# STM32F429.net
KiCad netlist of a schematic drawn in Altium Designer
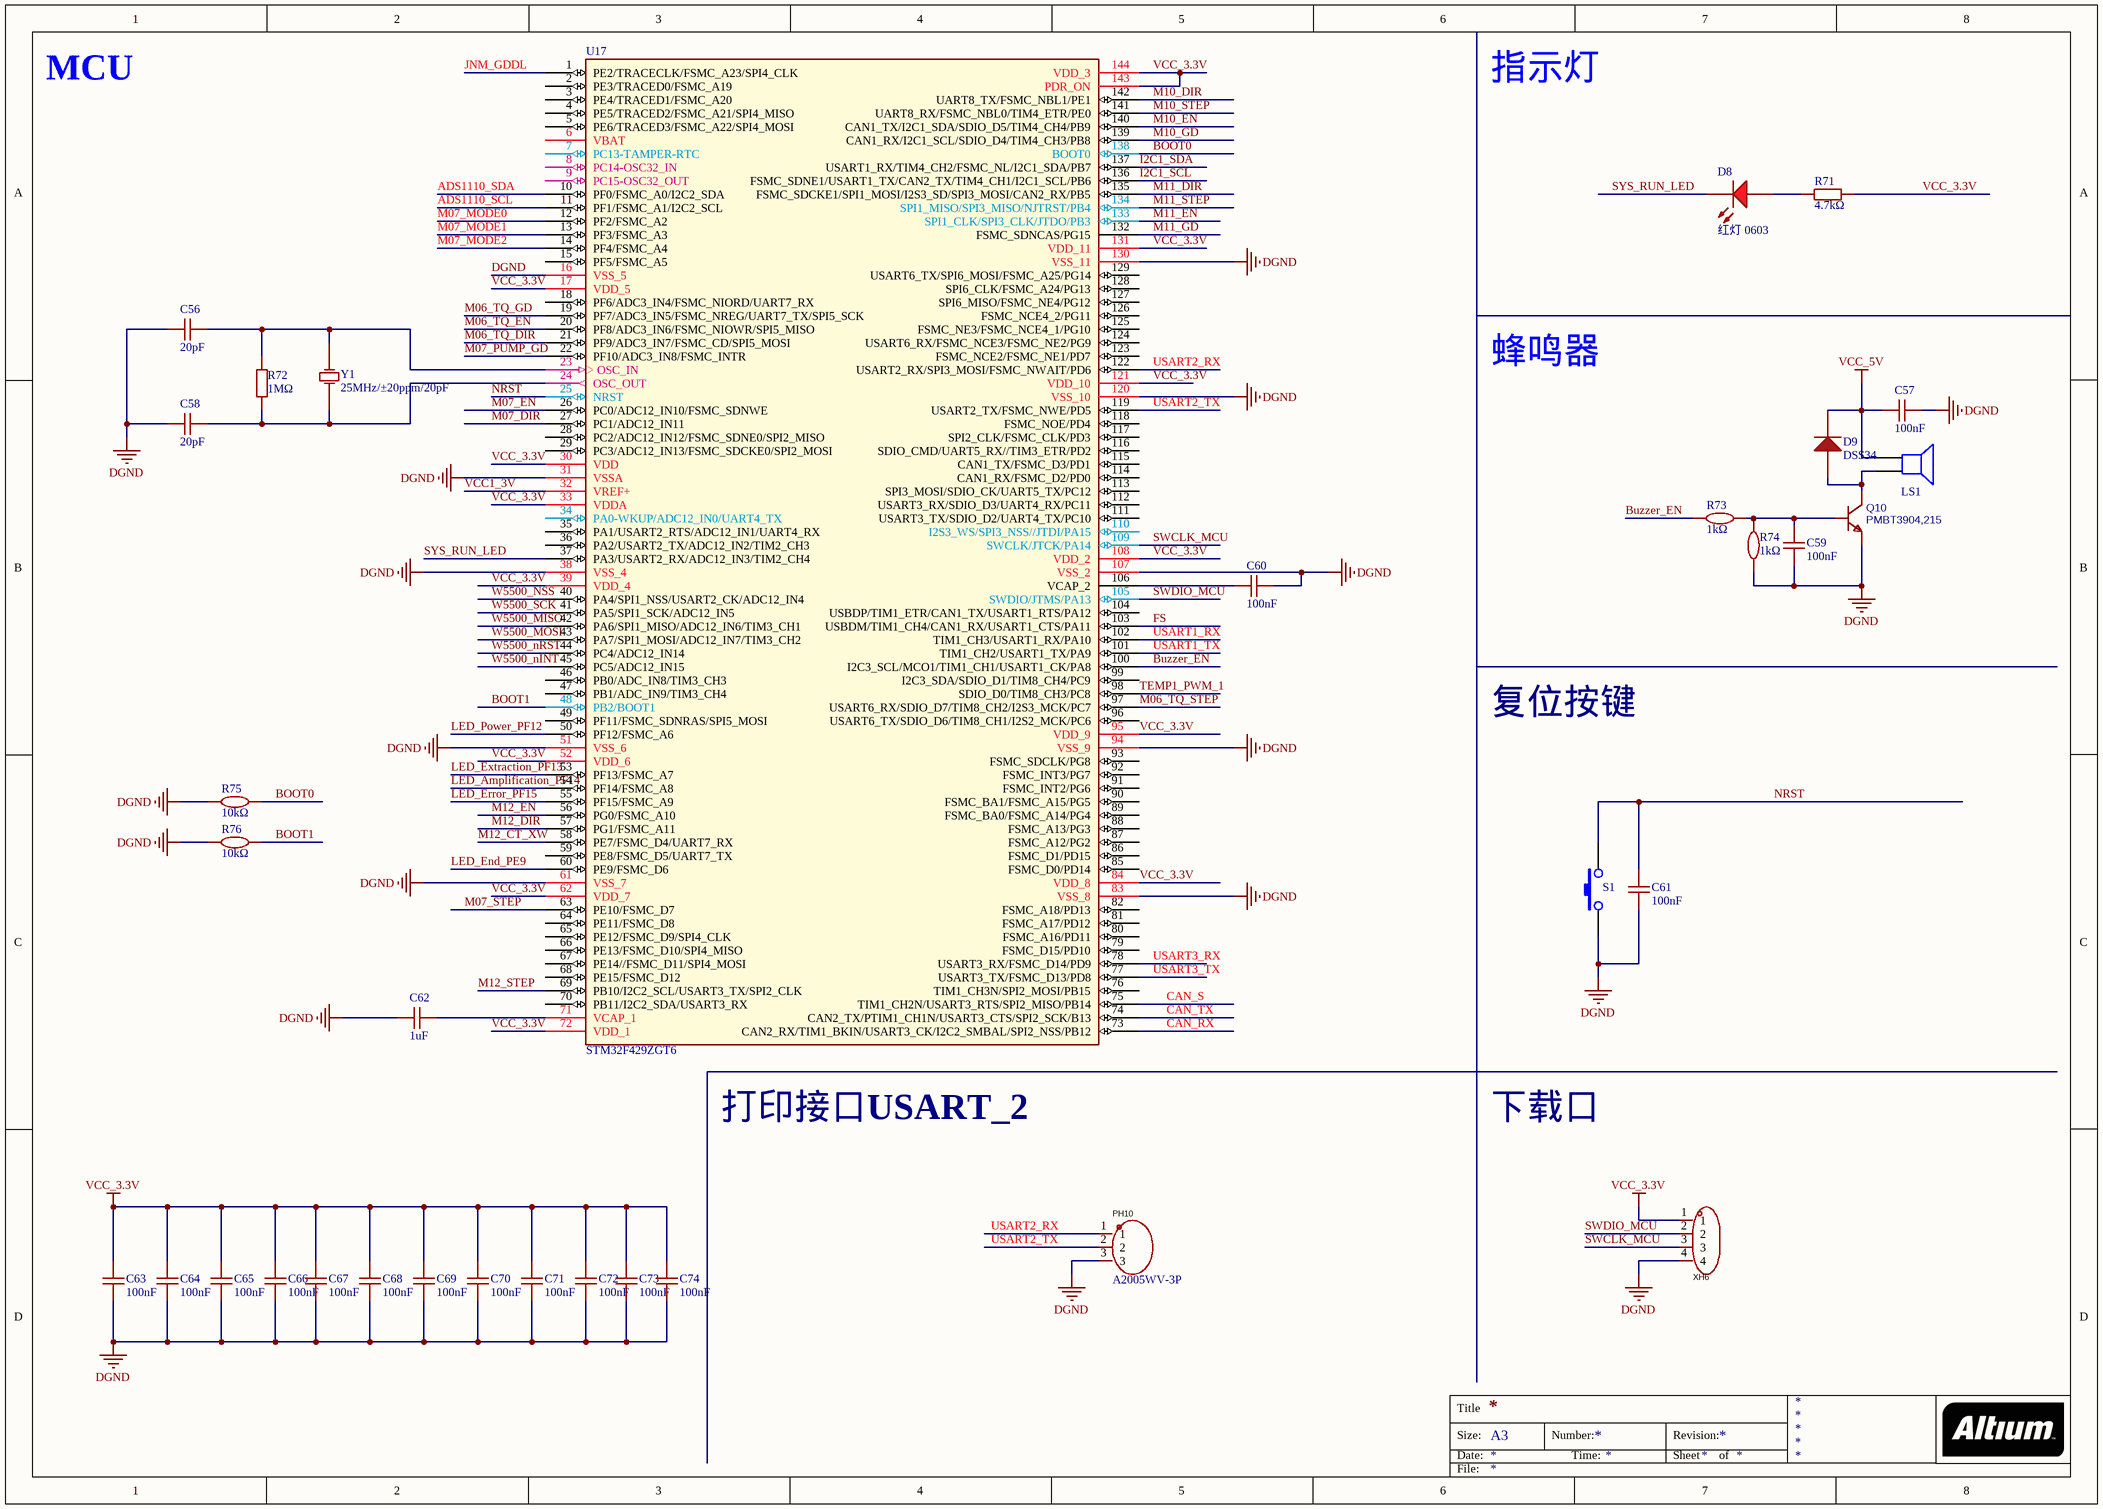
[diagram p0: STM32F429.SchDoc]

(export (version "E")
  (design (tool "Eeschema 10.0.6"))
  (components
    (comp (ref "C56")
      (value "20pF")
      (footprint "C0603")
      (description "贴片电容,X7R")
      (libsource (lib "XG_DW_POCT_2K10LED_3") (part "20pF/50V,C0603"))
    )
    (comp (ref "C57")
      (value "100nF")
      (footprint "C0603")
      (description "贴片电容,X7R")
      (libsource (lib "XG_DW_POCT_2K10LED_3") (part "100nF/50V,C0603"))
    )
    (comp (ref "C58")
      (value "20pF")
      (footprint "C0603")
      (description "贴片电容,X7R")
      (libsource (lib "XG_DW_POCT_2K10LED_3") (part "20pF/50V,C0603"))
    )
    (comp (ref "C59")
      (value "100nF")
      (footprint "C0603")
      (description "贴片电容,X7R")
      (libsource (lib "XG_DW_POCT_2K10LED_3") (part "100nF/50V,C0603"))
    )
    (comp (ref "C60")
      (value "100nF")
      (footprint "C0402")
      (description "贴片电容,X7R")
      (libsource (lib "XG_DW_POCT_2K10LED_3") (part "100nF/50V,C0402"))
    )
    (comp (ref "C61")
      (value "100nF")
      (footprint "C0402")
      (description "贴片电容,X7R")
      (libsource (lib "XG_DW_POCT_2K10LED_3") (part "100nF/50V,C0402"))
    )
    (comp (ref "C62")
      (value "1uF")
      (footprint "C0402")
      (description "贴片电容,X7R")
      (libsource (lib "XG_DW_POCT_2K10LED_3") (part "1uF/50V,C0402"))
    )
    (comp (ref "C63")
      (value "100nF")
      (footprint "C0402")
      (description "贴片电容,X7R")
      (libsource (lib "XG_DW_POCT_2K10LED_3") (part "100nF/50V,C0402"))
    )
    (comp (ref "C64")
      (value "100nF")
      (footprint "C0402")
      (description "贴片电容,X7R")
      (libsource (lib "XG_DW_POCT_2K10LED_3") (part "100nF/50V,C0402"))
    )
    (comp (ref "C65")
      (value "100nF")
      (footprint "C0402")
      (description "贴片电容,X7R")
      (libsource (lib "XG_DW_POCT_2K10LED_3") (part "100nF/50V,C0402"))
    )
    (comp (ref "C66")
      (value "100nF")
      (footprint "C0402")
      (description "贴片电容,X7R")
      (libsource (lib "XG_DW_POCT_2K10LED_3") (part "100nF/50V,C0402"))
    )
    (comp (ref "C67")
      (value "100nF")
      (footprint "C0402")
      (description "贴片电容,X7R")
      (libsource (lib "XG_DW_POCT_2K10LED_3") (part "100nF/50V,C0402"))
    )
    (comp (ref "C68")
      (value "100nF")
      (footprint "C0402")
      (description "贴片电容,X7R")
      (libsource (lib "XG_DW_POCT_2K10LED_3") (part "100nF/50V,C0402"))
    )
    (comp (ref "C69")
      (value "100nF")
      (footprint "C0402")
      (description "贴片电容,X7R")
      (libsource (lib "XG_DW_POCT_2K10LED_3") (part "100nF/50V,C0402"))
    )
    (comp (ref "C70")
      (value "100nF")
      (footprint "C0402")
      (description "贴片电容,X7R")
      (libsource (lib "XG_DW_POCT_2K10LED_3") (part "100nF/50V,C0402"))
    )
    (comp (ref "C71")
      (value "100nF")
      (footprint "C0402")
      (description "贴片电容,X7R")
      (libsource (lib "XG_DW_POCT_2K10LED_3") (part "100nF/50V,C0402"))
    )
    (comp (ref "C72")
      (value "100nF")
      (footprint "C0402")
      (description "贴片电容,X7R")
      (libsource (lib "XG_DW_POCT_2K10LED_3") (part "100nF/50V,C0402"))
    )
    (comp (ref "C73")
      (value "100nF")
      (footprint "C0402")
      (description "贴片电容,X7R")
      (libsource (lib "XG_DW_POCT_2K10LED_3") (part "100nF/50V,C0402"))
    )
    (comp (ref "C74")
      (value "100nF")
      (footprint "C0402")
      (description "贴片电容,X7R")
      (libsource (lib "XG_DW_POCT_2K10LED_3") (part "100nF/50V,C0402"))
    )
    (comp (ref "D8")
      (value "红灯 0603")
      (footprint "LED_0603")
      (description "发光二极管")
      (libsource (lib "XG_DW_POCT_2K10LED_3") (part "红灯 0603"))
    )
    (comp (ref "D9")
      (value "DSS34")
      (footprint "SOD-123")
      (description "肖特基二极管")
      (libsource (lib "XG_DW_POCT_2K10LED_3") (part "DSS34,SOD-123"))
    )
    (comp (ref "LS1")
      (value "~")
      (footprint "BUZZER")
      (description "Loudspeaker")
      (fields (field (name "PUBLISHER") "Altium Limited"))
      (libsource (lib "XG_DW_POCT_2K10LED_3") (part "Speaker"))
    )
    (comp (ref "PH10")
      (value "A2005WV-3P")
      (footprint "HDR-TH_3P-P2.00-V-M")
      (libsource (lib "XG_DW_POCT_2K10LED_3") (part "A2005WV-3P"))
    )
    (comp (ref "Q10")
      (value "PMBT3904,215")
      (footprint "SOT-23(SOT-23-3)")
      (libsource (lib "XG_DW_POCT_2K10LED_3") (part "PMBT3904,215"))
    )
    (comp (ref "R71")
      (value "4.7kΩ")
      (footprint "R0603")
      (description "贴片电阻")
      (libsource (lib "XG_DW_POCT_2K10LED_3") (part "4.7kΩ,R0603"))
    )
    (comp (ref "R72")
      (value "1MΩ")
      (footprint "R0603")
      (description "贴片电阻")
      (libsource (lib "XG_DW_POCT_2K10LED_3") (part "1MΩ,R0603"))
    )
    (comp (ref "R73")
      (value "1kΩ")
      (footprint "R0603")
      (description "电阻类型:厚膜电阻;阻值:1kΩ;精度:±1%;功率:125mW;最大工作电压:150V;温度系数:±100ppm/℃;")
      (libsource (lib "XG_DW_POCT_2K10LED_3") (part "1kΩ,R0603"))
    )
    (comp (ref "R74")
      (value "1kΩ")
      (footprint "R0603")
      (description "电阻类型:厚膜电阻;阻值:1kΩ;精度:±1%;功率:125mW;最大工作电压:150V;温度系数:±100ppm/℃;")
      (libsource (lib "XG_DW_POCT_2K10LED_3") (part "1kΩ,R0603"))
    )
    (comp (ref "R75")
      (value "10kΩ")
      (footprint "R0402")
      (description "电阻类型:厚膜电阻;阻值:10kΩ;精度:±1%;功率:100mW;最大工作电压:75V;温度系数:±100ppm/℃;")
      (libsource (lib "XG_DW_POCT_2K10LED_3") (part "10kΩ,R0402"))
    )
    (comp (ref "R76")
      (value "10kΩ")
      (footprint "R0402")
      (description "电阻类型:厚膜电阻;阻值:10kΩ;精度:±1%;功率:100mW;最大工作电压:75V;温度系数:±100ppm/℃;")
      (libsource (lib "XG_DW_POCT_2K10LED_3") (part "10kΩ,R0402"))
    )
    (comp (ref "S1")
      (value "~")
      (footprint "SW-S2 贴片")
      (libsource (lib "XG_DW_POCT_2K10LED_3") (part "SW-PB"))
    )
    (comp (ref "U17")
      (value "STM32F429ZGT6")
      (footprint "LQFP-144_20x20x05P")
      (description "ARM")
      (libsource (lib "XG_DW_POCT_2K10LED_3") (part "STM32F429ZGT6"))
    )
    (comp (ref "XH6")
      (value "A2541WV-4P")
      (footprint "HDR-TH_4P-P2.54-V-M")
      (description "C5346656")
      (libsource (lib "XG_DW_POCT_2K10LED_3") (part "A2541WV-4P"))
    )
    (comp (ref "Y1")
      (value "25MHz/±20ppm/20pF")
      (footprint "SMD-5032_2P")
      (description "X503225MSB2GI;无源晶振")
      (libsource (lib "XG_DW_POCT_2K10LED_3") (part "25MHz/±20ppm/20pF,SMD5032"))
    )
  )
  (nets
    (net (code "1") (name "/ADS1110_SCL") (class "Default")
      (node (ref "U17") (pin "11") (pinfunction "PF1/FSMC_A1/I2C2_SCL_11") (pintype "bidirectional"))
    )
    (net (code "2") (name "/ADS1110_SDA") (class "Default")
      (node (ref "U17") (pin "10") (pinfunction "PF0/FSMC_A0/I2C2_SDA_10") (pintype "bidirectional"))
    )
    (net (code "3") (name "/BOOT0") (class "Default")
      (node (ref "R75") (pin "1") (pinfunction "1_1") (pintype "passive"))
      (node (ref "U17") (pin "138") (pinfunction "BOOT0_138") (pintype "bidirectional"))
    )
    (net (code "4") (name "/BOOT1") (class "Default")
      (node (ref "R76") (pin "1") (pinfunction "1_1") (pintype "passive"))
      (node (ref "U17") (pin "48") (pinfunction "PB2/BOOT1_48") (pintype "bidirectional"))
    )
    (net (code "5") (name "/Buzzer_EN") (class "Default")
      (node (ref "R73") (pin "2") (pinfunction "2_2") (pintype "passive"))
      (node (ref "U17") (pin "100") (pinfunction "I2C3_SCL/MCO1/TIM1_CH1/USART1_CK/PA8_100") (pintype "bidirectional"))
    )
    (net (code "6") (name "/CAN_RX") (class "Default")
      (node (ref "U17") (pin "73") (pinfunction "CAN2_RX/TIM1_BKIN/USART3_CK/I2C2_SMBAL/SPI2_NSS/PB12_73") (pintype "bidirectional"))
    )
    (net (code "7") (name "/CAN_S") (class "Default")
      (node (ref "U17") (pin "75") (pinfunction "TIM1_CH2N/USART3_RTS/SPI2_MISO/PB14_75") (pintype "bidirectional"))
    )
    (net (code "8") (name "/CAN_TX") (class "Default")
      (node (ref "U17") (pin "74") (pinfunction "CAN2_TX/PTIM1_CH1N/USART3_CTS/SPI2_SCK/B13_74") (pintype "bidirectional"))
    )
    (net (code "9") (name "/FS") (class "Default")
      (node (ref "U17") (pin "103") (pinfunction "USBDM/TIM1_CH4/CAN1_RX/USART1_CTS/PA11_103") (pintype "bidirectional"))
    )
    (net (code "10") (name "/I2C1_SCL") (class "Default")
      (node (ref "U17") (pin "136") (pinfunction "FSMC_SDNE1/USART1_TX/CAN2_TX/TIM4_CH1/I2C1_SCL/PB6_136") (pintype "bidirectional"))
    )
    (net (code "11") (name "/I2C1_SDA") (class "Default")
      (node (ref "U17") (pin "137") (pinfunction "USART1_RX/TIM4_CH2/FSMC_NL/I2C1_SDA/PB7_137") (pintype "bidirectional"))
    )
    (net (code "12") (name "/JNM_GDDL") (class "Default")
      (node (ref "U17") (pin "1") (pinfunction "PE2/TRACECLK/FSMC_A23/SPI4_CLK_1") (pintype "bidirectional"))
    )
    (net (code "13") (name "/LED_Amplification_PF14") (class "Default")
      (node (ref "U17") (pin "54") (pinfunction "PF14/FSMC_A8_54") (pintype "bidirectional"))
    )
    (net (code "14") (name "/LED_End_PE9") (class "Default")
      (node (ref "U17") (pin "60") (pinfunction "PE9/FSMC_D6_60") (pintype "bidirectional"))
    )
    (net (code "15") (name "/LED_Error_PF15") (class "Default")
      (node (ref "U17") (pin "55") (pinfunction "PF15/FSMC_A9_55") (pintype "bidirectional"))
    )
    (net (code "16") (name "/LED_Extraction_PF13") (class "Default")
      (node (ref "U17") (pin "53") (pinfunction "PF13/FSMC_A7_53") (pintype "bidirectional"))
    )
    (net (code "17") (name "/LED_Power_PF12") (class "Default")
      (node (ref "U17") (pin "50") (pinfunction "PF12/FSMC_A6_50") (pintype "bidirectional"))
    )
    (net (code "18") (name "/M06_TQ_DIR") (class "Default")
      (node (ref "U17") (pin "21") (pinfunction "PF9/ADC3_IN7/FSMC_CD/SPI5_MOSI_21") (pintype "bidirectional"))
    )
    (net (code "19") (name "/M06_TQ_EN") (class "Default")
      (node (ref "U17") (pin "20") (pinfunction "PF8/ADC3_IN6/FSMC_NIOWR/SPI5_MISO_20") (pintype "bidirectional"))
    )
    (net (code "20") (name "/M06_TQ_GD") (class "Default")
      (node (ref "U17") (pin "19") (pinfunction "PF7/ADC3_IN5/FSMC_NREG/UART7_TX/SPI5_SCK_19") (pintype "bidirectional"))
    )
    (net (code "21") (name "/M06_TQ_STEP") (class "Default")
      (node (ref "U17") (pin "97") (pinfunction "USART6_RX/SDIO_D7/TIM8_CH2/I2S3_MCK/PC7_97") (pintype "bidirectional"))
    )
    (net (code "22") (name "/M07_DIR") (class "Default")
      (node (ref "U17") (pin "27") (pinfunction "PC1/ADC12_IN11_27") (pintype "bidirectional"))
    )
    (net (code "23") (name "/M07_EN") (class "Default")
      (node (ref "U17") (pin "26") (pinfunction "PC0/ADC12_IN10/FSMC_SDNWE_26") (pintype "bidirectional"))
    )
    (net (code "24") (name "/M07_MODE0") (class "Default")
      (node (ref "U17") (pin "12") (pinfunction "PF2/FSMC_A2_12") (pintype "bidirectional"))
    )
    (net (code "25") (name "/M07_MODE1") (class "Default")
      (node (ref "U17") (pin "13") (pinfunction "PF3/FSMC_A3_13") (pintype "bidirectional"))
    )
    (net (code "26") (name "/M07_MODE2") (class "Default")
      (node (ref "U17") (pin "14") (pinfunction "PF4/FSMC_A4_14") (pintype "bidirectional"))
    )
    (net (code "27") (name "/M07_PUMP_GD") (class "Default")
      (node (ref "U17") (pin "22") (pinfunction "PF10/ADC3_IN8/FSMC_INTR_22") (pintype "bidirectional"))
    )
    (net (code "28") (name "/M07_STEP") (class "Default")
      (node (ref "U17") (pin "63") (pinfunction "PE10/FSMC_D7_63") (pintype "bidirectional"))
    )
    (net (code "29") (name "/M10_DIR") (class "Default")
      (node (ref "U17") (pin "142") (pinfunction "UART8_TX/FSMC_NBL1/PE1_142") (pintype "bidirectional"))
    )
    (net (code "30") (name "/M10_EN") (class "Default")
      (node (ref "U17") (pin "140") (pinfunction "CAN1_TX/I2C1_SDA/SDIO_D5/TIM4_CH4/PB9_140") (pintype "bidirectional"))
    )
    (net (code "31") (name "/M10_GD") (class "Default")
      (node (ref "U17") (pin "139") (pinfunction "CAN1_RX/I2C1_SCL/SDIO_D4/TIM4_CH3/PB8_139") (pintype "bidirectional"))
    )
    (net (code "32") (name "/M10_STEP") (class "Default")
      (node (ref "U17") (pin "141") (pinfunction "UART8_RX/FSMC_NBL0/TIM4_ETR/PE0_141") (pintype "bidirectional"))
    )
    (net (code "33") (name "/M11_DIR") (class "Default")
      (node (ref "U17") (pin "135") (pinfunction "FSMC_SDCKE1/SPI1_MOSI/I2S3_SD/SPI3_MOSI/CAN2_RX/PB5_135") (pintype "bidirectional"))
    )
    (net (code "34") (name "/M11_EN") (class "Default")
      (node (ref "U17") (pin "133") (pinfunction "SPI1_CLK/SPI3_CLK/JTDO/PB3_133") (pintype "bidirectional"))
    )
    (net (code "35") (name "/M11_GD") (class "Default")
      (node (ref "U17") (pin "132") (pinfunction "FSMC_SDNCAS/PG15_132") (pintype "passive"))
    )
    (net (code "36") (name "/M11_STEP") (class "Default")
      (node (ref "U17") (pin "134") (pinfunction "SPI1_MISO/SPI3_MISO/NJTRST/PB4_134") (pintype "bidirectional"))
    )
    (net (code "37") (name "/M12_CT_XW") (class "Default")
      (node (ref "U17") (pin "58") (pinfunction "PE7/FSMC_D4/UART7_RX_58") (pintype "bidirectional"))
    )
    (net (code "38") (name "/M12_DIR") (class "Default")
      (node (ref "U17") (pin "57") (pinfunction "PG1/FSMC_A11_57") (pintype "bidirectional"))
    )
    (net (code "39") (name "/M12_EN") (class "Default")
      (node (ref "U17") (pin "56") (pinfunction "PG0/FSMC_A10_56") (pintype "bidirectional"))
    )
    (net (code "40") (name "/M12_STEP") (class "Default")
      (node (ref "U17") (pin "69") (pinfunction "PB10/I2C2_SCL/USART3_TX/SPI2_CLK_69") (pintype "bidirectional"))
    )
    (net (code "41") (name "/NRST") (class "Default")
      (node (ref "C61") (pin "2") (pinfunction "2_2") (pintype "passive"))
      (node (ref "S1") (pin "2") (pinfunction "2_2") (pintype "passive"))
      (node (ref "U17") (pin "25") (pinfunction "NRST_25") (pintype "bidirectional"))
    )
    (net (code "42") (name "/SWCLK_MCU") (class "Default")
      (node (ref "U17") (pin "109") (pinfunction "SWCLK/JTCK/PA14_109") (pintype "bidirectional"))
      (node (ref "XH6") (pin "3") (pinfunction "3_3") (pintype "passive"))
    )
    (net (code "43") (name "/SWDIO_MCU") (class "Default")
      (node (ref "U17") (pin "105") (pinfunction "SWDIO/JTMS/PA13_105") (pintype "bidirectional"))
      (node (ref "XH6") (pin "2") (pinfunction "2_2") (pintype "passive"))
    )
    (net (code "44") (name "/SYS_RUN_LED") (class "Default")
      (node (ref "D8") (pin "K") (pinfunction "K_K") (pintype "passive"))
      (node (ref "U17") (pin "37") (pinfunction "PA3/USART2_RX/ADC12_IN3/TIM2_CH4_37") (pintype "bidirectional"))
    )
    (net (code "45") (name "/TEMP1_PWM_1") (class "Default")
      (node (ref "U17") (pin "98") (pinfunction "SDIO_D0/TIM8_CH3/PC8_98") (pintype "bidirectional"))
    )
    (net (code "46") (name "/USART1_RX") (class "Default")
      (node (ref "U17") (pin "102") (pinfunction "TIM1_CH3/USART1_RX/PA10_102") (pintype "bidirectional"))
    )
    (net (code "47") (name "/USART1_TX") (class "Default")
      (node (ref "U17") (pin "101") (pinfunction "TIM1_CH2/USART1_TX/PA9_101") (pintype "bidirectional"))
    )
    (net (code "48") (name "/USART2_RX") (class "Default")
      (node (ref "PH10") (pin "1") (pinfunction "1_1") (pintype "passive"))
      (node (ref "U17") (pin "122") (pinfunction "USART2_RX/SPI3_MOSI/FSMC_NWAIT/PD6_122") (pintype "bidirectional"))
    )
    (net (code "49") (name "/USART2_TX") (class "Default")
      (node (ref "PH10") (pin "2") (pinfunction "2_2") (pintype "passive"))
      (node (ref "U17") (pin "119") (pinfunction "USART2_TX/FSMC_NWE/PD5_119") (pintype "bidirectional"))
    )
    (net (code "50") (name "/USART3_RX") (class "Default")
      (node (ref "U17") (pin "78") (pinfunction "USART3_RX/FSMC_D14/PD9_78") (pintype "bidirectional"))
    )
    (net (code "51") (name "/USART3_TX") (class "Default")
      (node (ref "U17") (pin "77") (pinfunction "USART3_TX/FSMC_D13/PD8_77") (pintype "bidirectional"))
    )
    (net (code "52") (name "/VCC1_3V") (class "Default")
      (node (ref "U17") (pin "32") (pinfunction "VREF+_32") (pintype "power_in"))
    )
    (net (code "53") (name "/W5500_MISO") (class "Default")
      (node (ref "U17") (pin "42") (pinfunction "PA6/SPI1_MISO/ADC12_IN6/TIM3_CH1_42") (pintype "bidirectional"))
    )
    (net (code "54") (name "/W5500_MOSI") (class "Default")
      (node (ref "U17") (pin "43") (pinfunction "PA7/SPI1_MOSI/ADC12_IN7/TIM3_CH2_43") (pintype "bidirectional"))
    )
    (net (code "55") (name "/W5500_NSS") (class "Default")
      (node (ref "U17") (pin "40") (pinfunction "PA4/SPI1_NSS/USART2_CK/ADC12_IN4_40") (pintype "bidirectional"))
    )
    (net (code "56") (name "/W5500_SCK") (class "Default")
      (node (ref "U17") (pin "41") (pinfunction "PA5/SPI1_SCK/ADC12_IN5_41") (pintype "bidirectional"))
    )
    (net (code "57") (name "/W5500_nINT") (class "Default")
      (node (ref "U17") (pin "45") (pinfunction "PC5/ADC12_IN15_45") (pintype "bidirectional"))
    )
    (net (code "58") (name "/W5500_nRST") (class "Default")
      (node (ref "U17") (pin "44") (pinfunction "PC4/ADC12_IN14_44") (pintype "bidirectional"))
    )
    (net (code "59") (name "DGND") (class "Default")
      (node (ref "C56") (pin "1") (pinfunction "1_1") (pintype "passive"))
      (node (ref "C57") (pin "2") (pinfunction "2_2") (pintype "passive"))
      (node (ref "C58") (pin "1") (pinfunction "1_1") (pintype "passive"))
      (node (ref "C59") (pin "1") (pinfunction "1_1") (pintype "passive"))
      (node (ref "C60") (pin "2") (pinfunction "2_2") (pintype "passive"))
      (node (ref "C61") (pin "1") (pinfunction "1_1") (pintype "passive"))
      (node (ref "C62") (pin "1") (pinfunction "1_1") (pintype "passive"))
      (node (ref "C63") (pin "1") (pinfunction "1_1") (pintype "passive"))
      (node (ref "C64") (pin "1") (pinfunction "1_1") (pintype "passive"))
      (node (ref "C65") (pin "1") (pinfunction "1_1") (pintype "passive"))
      (node (ref "C66") (pin "1") (pinfunction "1_1") (pintype "passive"))
      (node (ref "C67") (pin "1") (pinfunction "1_1") (pintype "passive"))
      (node (ref "C68") (pin "1") (pinfunction "1_1") (pintype "passive"))
      (node (ref "C69") (pin "1") (pinfunction "1_1") (pintype "passive"))
      (node (ref "C70") (pin "1") (pinfunction "1_1") (pintype "passive"))
      (node (ref "C71") (pin "1") (pinfunction "1_1") (pintype "passive"))
      (node (ref "C72") (pin "1") (pinfunction "1_1") (pintype "passive"))
      (node (ref "C73") (pin "1") (pinfunction "1_1") (pintype "passive"))
      (node (ref "C74") (pin "1") (pinfunction "1_1") (pintype "passive"))
      (node (ref "PH10") (pin "3") (pinfunction "3_3") (pintype "passive"))
      (node (ref "Q10") (pin "2") (pinfunction "2_2") (pintype "passive"))
      (node (ref "R74") (pin "2") (pinfunction "2_2") (pintype "passive"))
      (node (ref "R75") (pin "2") (pinfunction "2_2") (pintype "passive"))
      (node (ref "R76") (pin "2") (pinfunction "2_2") (pintype "passive"))
      (node (ref "S1") (pin "1") (pinfunction "1_1") (pintype "passive"))
      (node (ref "U17") (pin "107") (pinfunction "VSS_2_107") (pintype "power_in"))
      (node (ref "U17") (pin "120") (pinfunction "VSS_10_120") (pintype "power_in"))
      (node (ref "U17") (pin "130") (pinfunction "VSS_11_130") (pintype "power_in"))
      (node (ref "U17") (pin "16") (pinfunction "VSS_5_16") (pintype "power_in"))
      (node (ref "U17") (pin "31") (pinfunction "VSSA_31") (pintype "power_in"))
      (node (ref "U17") (pin "38") (pinfunction "VSS_4_38") (pintype "power_in"))
      (node (ref "U17") (pin "51") (pinfunction "VSS_6_51") (pintype "power_in"))
      (node (ref "U17") (pin "61") (pinfunction "VSS_7_61") (pintype "power_in"))
      (node (ref "U17") (pin "83") (pinfunction "VSS_8_83") (pintype "power_in"))
      (node (ref "U17") (pin "94") (pinfunction "VSS_9_94") (pintype "power_in"))
      (node (ref "XH6") (pin "4") (pinfunction "4_4") (pintype "passive"))
    )
    (net (code "60") (name "Net-(C59-Pad2)") (class "Default")
      (node (ref "C59") (pin "2") (pinfunction "2_2") (pintype "passive"))
      (node (ref "Q10") (pin "1") (pinfunction "1_1") (pintype "passive"))
      (node (ref "R73") (pin "1") (pinfunction "1_1") (pintype "passive"))
      (node (ref "R74") (pin "1") (pinfunction "1_1") (pintype "passive"))
    )
    (net (code "61") (name "Net-(D8-PadA)") (class "Default")
      (node (ref "D8") (pin "A") (pinfunction "A_A") (pintype "passive"))
      (node (ref "R71") (pin "1") (pinfunction "1_1") (pintype "passive"))
    )
    (net (code "62") (name "Net-(D9-A)") (class "Default")
      (node (ref "D9") (pin "1") (pinfunction "A_1") (pintype "passive"))
      (node (ref "LS1") (pin "2") (pinfunction "2_2") (pintype "passive"))
      (node (ref "Q10") (pin "3") (pinfunction "3_3") (pintype "passive"))
    )
    (net (code "63") (name "Net-(U17-OSC_IN)") (class "Default")
      (node (ref "C56") (pin "2") (pinfunction "2_2") (pintype "passive"))
      (node (ref "R72") (pin "2") (pinfunction "2_2") (pintype "passive"))
      (node (ref "U17") (pin "23") (pinfunction "OSC_IN_23") (pintype "input"))
      (node (ref "Y1") (pin "2") (pinfunction "OSC2_2") (pintype "passive"))
    )
    (net (code "64") (name "Net-(U17-OSC_OUT)") (class "Default")
      (node (ref "C58") (pin "2") (pinfunction "2_2") (pintype "passive"))
      (node (ref "R72") (pin "1") (pinfunction "1_1") (pintype "passive"))
      (node (ref "U17") (pin "24") (pinfunction "OSC_OUT_24") (pintype "output"))
      (node (ref "Y1") (pin "1") (pinfunction "OSC1_1") (pintype "passive"))
    )
    (net (code "65") (name "Net-(U17-VCAP_1)") (class "Default")
      (node (ref "C62") (pin "2") (pinfunction "2_2") (pintype "passive"))
      (node (ref "U17") (pin "71") (pinfunction "VCAP_1_71") (pintype "power_in"))
    )
    (net (code "66") (name "Net-(U17-VCAP_2)") (class "Default")
      (node (ref "C60") (pin "1") (pinfunction "1_1") (pintype "passive"))
      (node (ref "U17") (pin "106") (pinfunction "VCAP_2_106") (pintype "tri_state"))
    )
    (net (code "67") (name "VCC_3.3V") (class "Default")
      (node (ref "C63") (pin "2") (pinfunction "2_2") (pintype "passive"))
      (node (ref "C64") (pin "2") (pinfunction "2_2") (pintype "passive"))
      (node (ref "C65") (pin "2") (pinfunction "2_2") (pintype "passive"))
      (node (ref "C66") (pin "2") (pinfunction "2_2") (pintype "passive"))
      (node (ref "C67") (pin "2") (pinfunction "2_2") (pintype "passive"))
      (node (ref "C68") (pin "2") (pinfunction "2_2") (pintype "passive"))
      (node (ref "C69") (pin "2") (pinfunction "2_2") (pintype "passive"))
      (node (ref "C70") (pin "2") (pinfunction "2_2") (pintype "passive"))
      (node (ref "C71") (pin "2") (pinfunction "2_2") (pintype "passive"))
      (node (ref "C72") (pin "2") (pinfunction "2_2") (pintype "passive"))
      (node (ref "C73") (pin "2") (pinfunction "2_2") (pintype "passive"))
      (node (ref "C74") (pin "2") (pinfunction "2_2") (pintype "passive"))
      (node (ref "R71") (pin "2") (pinfunction "2_2") (pintype "passive"))
      (node (ref "U17") (pin "108") (pinfunction "VDD_2_108") (pintype "power_in"))
      (node (ref "U17") (pin "121") (pinfunction "VDD_10_121") (pintype "power_in"))
      (node (ref "U17") (pin "131") (pinfunction "VDD_11_131") (pintype "power_in"))
      (node (ref "U17") (pin "143") (pinfunction "PDR_ON_143") (pintype "power_in"))
      (node (ref "U17") (pin "144") (pinfunction "VDD_3_144") (pintype "power_in"))
      (node (ref "U17") (pin "17") (pinfunction "VDD_5_17") (pintype "power_in"))
      (node (ref "U17") (pin "30") (pinfunction "VDD_30") (pintype "power_in"))
      (node (ref "U17") (pin "33") (pinfunction "VDDA_33") (pintype "power_in"))
      (node (ref "U17") (pin "39") (pinfunction "VDD_4_39") (pintype "power_in"))
      (node (ref "U17") (pin "52") (pinfunction "VDD_6_52") (pintype "power_in"))
      (node (ref "U17") (pin "62") (pinfunction "VDD_7_62") (pintype "power_in"))
      (node (ref "U17") (pin "72") (pinfunction "VDD_1_72") (pintype "power_in"))
      (node (ref "U17") (pin "84") (pinfunction "VDD_8_84") (pintype "power_in"))
      (node (ref "U17") (pin "95") (pinfunction "VDD_9_95") (pintype "power_in"))
      (node (ref "XH6") (pin "1") (pinfunction "1_1") (pintype "passive"))
    )
    (net (code "68") (name "VCC_5V") (class "Default")
      (node (ref "C57") (pin "1") (pinfunction "1_1") (pintype "passive"))
      (node (ref "D9") (pin "2") (pinfunction "K_2") (pintype "passive"))
      (node (ref "LS1") (pin "1") (pinfunction "1_1") (pintype "passive"))
    )
    (net (code "69") (name "unconnected-(U17-CAN1_RX{slash}FSMC_D2{slash}PD0-Pad114)") (class "Default")
      (node (ref "U17") (pin "114") (pinfunction "CAN1_RX/FSMC_D2/PD0_114") (pintype "bidirectional"))
    )
    (net (code "70") (name "unconnected-(U17-CAN1_TX{slash}FSMC_D3{slash}PD1-Pad115)") (class "Default")
      (node (ref "U17") (pin "115") (pinfunction "CAN1_TX/FSMC_D3/PD1_115") (pintype "bidirectional"))
    )
    (net (code "71") (name "unconnected-(U17-FSMC_A12{slash}PG2-Pad87)") (class "Default")
      (node (ref "U17") (pin "87") (pinfunction "FSMC_A12/PG2_87") (pintype "bidirectional"))
    )
    (net (code "72") (name "unconnected-(U17-FSMC_A13{slash}PG3-Pad88)") (class "Default")
      (node (ref "U17") (pin "88") (pinfunction "FSMC_A13/PG3_88") (pintype "bidirectional"))
    )
    (net (code "73") (name "unconnected-(U17-FSMC_A16{slash}PD11-Pad80)") (class "Default")
      (node (ref "U17") (pin "80") (pinfunction "FSMC_A16/PD11_80") (pintype "bidirectional"))
    )
    (net (code "74") (name "unconnected-(U17-FSMC_A17{slash}PD12-Pad81)") (class "Default")
      (node (ref "U17") (pin "81") (pinfunction "FSMC_A17/PD12_81") (pintype "bidirectional"))
    )
    (net (code "75") (name "unconnected-(U17-FSMC_A18{slash}PD13-Pad82)") (class "Default")
      (node (ref "U17") (pin "82") (pinfunction "FSMC_A18/PD13_82") (pintype "bidirectional"))
    )
    (net (code "76") (name "unconnected-(U17-FSMC_BA0{slash}FSMC_A14{slash}PG4-Pad89)") (class "Default")
      (node (ref "U17") (pin "89") (pinfunction "FSMC_BA0/FSMC_A14/PG4_89") (pintype "bidirectional"))
    )
    (net (code "77") (name "unconnected-(U17-FSMC_BA1{slash}FSMC_A15{slash}PG5-Pad90)") (class "Default")
      (node (ref "U17") (pin "90") (pinfunction "FSMC_BA1/FSMC_A15/PG5_90") (pintype "bidirectional"))
    )
    (net (code "78") (name "unconnected-(U17-FSMC_D0{slash}PD14-Pad85)") (class "Default")
      (node (ref "U17") (pin "85") (pinfunction "FSMC_D0/PD14_85") (pintype "bidirectional"))
    )
    (net (code "79") (name "unconnected-(U17-FSMC_D1{slash}PD15-Pad86)") (class "Default")
      (node (ref "U17") (pin "86") (pinfunction "FSMC_D1/PD15_86") (pintype "bidirectional"))
    )
    (net (code "80") (name "unconnected-(U17-FSMC_D15{slash}PD10-Pad79)") (class "Default")
      (node (ref "U17") (pin "79") (pinfunction "FSMC_D15/PD10_79") (pintype "bidirectional"))
    )
    (net (code "81") (name "unconnected-(U17-FSMC_INT2{slash}PG6-Pad91)") (class "Default")
      (node (ref "U17") (pin "91") (pinfunction "FSMC_INT2/PG6_91") (pintype "bidirectional"))
    )
    (net (code "82") (name "unconnected-(U17-FSMC_INT3{slash}PG7-Pad92)") (class "Default")
      (node (ref "U17") (pin "92") (pinfunction "FSMC_INT3/PG7_92") (pintype "bidirectional"))
    )
    (net (code "83") (name "unconnected-(U17-FSMC_NCE2{slash}FSMC_NE1{slash}PD7-Pad123)") (class "Default")
      (node (ref "U17") (pin "123") (pinfunction "FSMC_NCE2/FSMC_NE1/PD7_123") (pintype "bidirectional"))
    )
    (net (code "84") (name "unconnected-(U17-FSMC_NCE4_2{slash}PG11-Pad126)") (class "Default")
      (node (ref "U17") (pin "126") (pinfunction "FSMC_NCE4_2/PG11_126") (pintype "bidirectional"))
    )
    (net (code "85") (name "unconnected-(U17-FSMC_NE3{slash}FSMC_NCE4_1{slash}PG10-Pad125)") (class "Default")
      (node (ref "U17") (pin "125") (pinfunction "FSMC_NE3/FSMC_NCE4_1/PG10_125") (pintype "bidirectional"))
    )
    (net (code "86") (name "unconnected-(U17-FSMC_NOE{slash}PD4-Pad118)") (class "Default")
      (node (ref "U17") (pin "118") (pinfunction "FSMC_NOE/PD4_118") (pintype "bidirectional"))
    )
    (net (code "87") (name "unconnected-(U17-FSMC_SDCLK{slash}PG8-Pad93)") (class "Default")
      (node (ref "U17") (pin "93") (pinfunction "FSMC_SDCLK/PG8_93") (pintype "bidirectional"))
    )
    (net (code "88") (name "unconnected-(U17-I2C3_SDA{slash}SDIO_D1{slash}TIM8_CH4{slash}PC9-Pad99)") (class "Default")
      (node (ref "U17") (pin "99") (pinfunction "I2C3_SDA/SDIO_D1/TIM8_CH4/PC9_99") (pintype "bidirectional"))
    )
    (net (code "89") (name "unconnected-(U17-I2S3_WS{slash}SPI3_NSS{slash}{slash}JTDI{slash}PA15-Pad110)") (class "Default")
      (node (ref "U17") (pin "110") (pinfunction "I2S3_WS/SPI3_NSS//JTDI/PA15_110") (pintype "bidirectional"))
    )
    (net (code "90") (name "unconnected-(U17-PA0-WKUP{slash}ADC12_IN0{slash}UART4_TX-Pad34)") (class "Default")
      (node (ref "U17") (pin "34") (pinfunction "PA0-WKUP/ADC12_IN0/UART4_TX_34") (pintype "bidirectional"))
    )
    (net (code "91") (name "unconnected-(U17-PA1{slash}USART2_RTS{slash}ADC12_IN1{slash}UART4_RX-Pad35)") (class "Default")
      (node (ref "U17") (pin "35") (pinfunction "PA1/USART2_RTS/ADC12_IN1/UART4_RX_35") (pintype "bidirectional"))
    )
    (net (code "92") (name "unconnected-(U17-PA2{slash}USART2_TX{slash}ADC12_IN2{slash}TIM2_CH3-Pad36)") (class "Default")
      (node (ref "U17") (pin "36") (pinfunction "PA2/USART2_TX/ADC12_IN2/TIM2_CH3_36") (pintype "bidirectional"))
    )
    (net (code "93") (name "unconnected-(U17-PB0{slash}ADC_IN8{slash}TIM3_CH3-Pad46)") (class "Default")
      (node (ref "U17") (pin "46") (pinfunction "PB0/ADC_IN8/TIM3_CH3_46") (pintype "bidirectional"))
    )
    (net (code "94") (name "unconnected-(U17-PB1{slash}ADC_IN9{slash}TIM3_CH4-Pad47)") (class "Default")
      (node (ref "U17") (pin "47") (pinfunction "PB1/ADC_IN9/TIM3_CH4_47") (pintype "bidirectional"))
    )
    (net (code "95") (name "unconnected-(U17-PB11{slash}I2C2_SDA{slash}USART3_RX-Pad70)") (class "Default")
      (node (ref "U17") (pin "70") (pinfunction "PB11/I2C2_SDA/USART3_RX_70") (pintype "bidirectional"))
    )
    (net (code "96") (name "unconnected-(U17-PC2{slash}ADC12_IN12{slash}FSMC_SDNE0{slash}SPI2_MISO-Pad28)") (class "Default")
      (node (ref "U17") (pin "28") (pinfunction "PC2/ADC12_IN12/FSMC_SDNE0/SPI2_MISO_28") (pintype "bidirectional"))
    )
    (net (code "97") (name "unconnected-(U17-PC3{slash}ADC12_IN13{slash}FSMC_SDCKE0{slash}SPI2_MOSI-Pad29)") (class "Default")
      (node (ref "U17") (pin "29") (pinfunction "PC3/ADC12_IN13/FSMC_SDCKE0/SPI2_MOSI_29") (pintype "bidirectional"))
    )
    (net (code "98") (name "unconnected-(U17-PC13-TAMPER-RTC-Pad7)") (class "Default")
      (node (ref "U17") (pin "7") (pinfunction "PC13-TAMPER-RTC_7") (pintype "bidirectional"))
    )
    (net (code "99") (name "unconnected-(U17-PC14-OSC32_IN-Pad8)") (class "Default")
      (node (ref "U17") (pin "8") (pinfunction "PC14-OSC32_IN_8") (pintype "bidirectional"))
    )
    (net (code "100") (name "unconnected-(U17-PC15-OSC32_OUT-Pad9)") (class "Default")
      (node (ref "U17") (pin "9") (pinfunction "PC15-OSC32_OUT_9") (pintype "bidirectional"))
    )
    (net (code "101") (name "unconnected-(U17-PE3{slash}TRACED0{slash}FSMC_A19-Pad2)") (class "Default")
      (node (ref "U17") (pin "2") (pinfunction "PE3/TRACED0/FSMC_A19_2") (pintype "bidirectional"))
    )
    (net (code "102") (name "unconnected-(U17-PE4{slash}TRACED1{slash}FSMC_A20-Pad3)") (class "Default")
      (node (ref "U17") (pin "3") (pinfunction "PE4/TRACED1/FSMC_A20_3") (pintype "bidirectional"))
    )
    (net (code "103") (name "unconnected-(U17-PE5{slash}TRACED2{slash}FSMC_A21{slash}SPI4_MISO-Pad4)") (class "Default")
      (node (ref "U17") (pin "4") (pinfunction "PE5/TRACED2/FSMC_A21/SPI4_MISO_4") (pintype "bidirectional"))
    )
    (net (code "104") (name "unconnected-(U17-PE6{slash}TRACED3{slash}FSMC_A22{slash}SPI4_MOSI-Pad5)") (class "Default")
      (node (ref "U17") (pin "5") (pinfunction "PE6/TRACED3/FSMC_A22/SPI4_MOSI_5") (pintype "bidirectional"))
    )
    (net (code "105") (name "unconnected-(U17-PE8{slash}FSMC_D5{slash}UART7_TX-Pad59)") (class "Default")
      (node (ref "U17") (pin "59") (pinfunction "PE8/FSMC_D5/UART7_TX_59") (pintype "bidirectional"))
    )
    (net (code "106") (name "unconnected-(U17-PE11{slash}FSMC_D8-Pad64)") (class "Default")
      (node (ref "U17") (pin "64") (pinfunction "PE11/FSMC_D8_64") (pintype "bidirectional"))
    )
    (net (code "107") (name "unconnected-(U17-PE12{slash}FSMC_D9{slash}SPI4_CLK-Pad65)") (class "Default")
      (node (ref "U17") (pin "65") (pinfunction "PE12/FSMC_D9/SPI4_CLK_65") (pintype "bidirectional"))
    )
    (net (code "108") (name "unconnected-(U17-PE13{slash}FSMC_D10{slash}SPI4_MISO-Pad66)") (class "Default")
      (node (ref "U17") (pin "66") (pinfunction "PE13/FSMC_D10/SPI4_MISO_66") (pintype "bidirectional"))
    )
    (net (code "109") (name "unconnected-(U17-PE14{slash}{slash}FSMC_D11{slash}SPI4_MOSI-Pad67)") (class "Default")
      (node (ref "U17") (pin "67") (pinfunction "PE14//FSMC_D11/SPI4_MOSI_67") (pintype "bidirectional"))
    )
    (net (code "110") (name "unconnected-(U17-PE15{slash}FSMC_D12-Pad68)") (class "Default")
      (node (ref "U17") (pin "68") (pinfunction "PE15/FSMC_D12_68") (pintype "bidirectional"))
    )
    (net (code "111") (name "unconnected-(U17-PF5{slash}FSMC_A5-Pad15)") (class "Default")
      (node (ref "U17") (pin "15") (pinfunction "PF5/FSMC_A5_15") (pintype "bidirectional"))
    )
    (net (code "112") (name "unconnected-(U17-PF6{slash}ADC3_IN4{slash}FSMC_NIORD{slash}UART7_RX-Pad18)") (class "Default")
      (node (ref "U17") (pin "18") (pinfunction "PF6/ADC3_IN4/FSMC_NIORD/UART7_RX_18") (pintype "bidirectional"))
    )
    (net (code "113") (name "unconnected-(U17-PF11{slash}FSMC_SDNRAS{slash}SPI5_MOSI-Pad49)") (class "Default")
      (node (ref "U17") (pin "49") (pinfunction "PF11/FSMC_SDNRAS/SPI5_MOSI_49") (pintype "bidirectional"))
    )
    (net (code "114") (name "unconnected-(U17-SDIO_CMD{slash}UART5_RX{slash}{slash}TIM3_ETR{slash}PD2-Pad116)") (class "Default")
      (node (ref "U17") (pin "116") (pinfunction "SDIO_CMD/UART5_RX//TIM3_ETR/PD2_116") (pintype "bidirectional"))
    )
    (net (code "115") (name "unconnected-(U17-SPI2_CLK{slash}FSMC_CLK{slash}PD3-Pad117)") (class "Default")
      (node (ref "U17") (pin "117") (pinfunction "SPI2_CLK/FSMC_CLK/PD3_117") (pintype "bidirectional"))
    )
    (net (code "116") (name "unconnected-(U17-SPI3_MOSI{slash}SDIO_CK{slash}UART5_TX{slash}PC12-Pad113)") (class "Default")
      (node (ref "U17") (pin "113") (pinfunction "SPI3_MOSI/SDIO_CK/UART5_TX/PC12_113") (pintype "bidirectional"))
    )
    (net (code "117") (name "unconnected-(U17-SPI6_CLK{slash}FSMC_A24{slash}PG13-Pad128)") (class "Default")
      (node (ref "U17") (pin "128") (pinfunction "SPI6_CLK/FSMC_A24/PG13_128") (pintype "bidirectional"))
    )
    (net (code "118") (name "unconnected-(U17-SPI6_MISO{slash}FSMC_NE4{slash}PG12-Pad127)") (class "Default")
      (node (ref "U17") (pin "127") (pinfunction "SPI6_MISO/FSMC_NE4/PG12_127") (pintype "bidirectional"))
    )
    (net (code "119") (name "unconnected-(U17-TIM1_CH3N{slash}SPI2_MOSI{slash}PB15-Pad76)") (class "Default")
      (node (ref "U17") (pin "76") (pinfunction "TIM1_CH3N/SPI2_MOSI/PB15_76") (pintype "bidirectional"))
    )
    (net (code "120") (name "unconnected-(U17-USART3_RX{slash}SDIO_D3{slash}UART4_RX{slash}PC11-Pad112)") (class "Default")
      (node (ref "U17") (pin "112") (pinfunction "USART3_RX/SDIO_D3/UART4_RX/PC11_112") (pintype "bidirectional"))
    )
    (net (code "121") (name "unconnected-(U17-USART3_TX{slash}SDIO_D2{slash}UART4_TX{slash}PC10-Pad111)") (class "Default")
      (node (ref "U17") (pin "111") (pinfunction "USART3_TX/SDIO_D2/UART4_TX/PC10_111") (pintype "bidirectional"))
    )
    (net (code "122") (name "unconnected-(U17-USART6_RX{slash}FSMC_NCE3{slash}FSMC_NE2{slash}PG9-Pad124)") (class "Default")
      (node (ref "U17") (pin "124") (pinfunction "USART6_RX/FSMC_NCE3/FSMC_NE2/PG9_124") (pintype "bidirectional"))
    )
    (net (code "123") (name "unconnected-(U17-USART6_TX{slash}SDIO_D6{slash}TIM8_CH1{slash}I2S2_MCK{slash}PC6-Pad96)") (class "Default")
      (node (ref "U17") (pin "96") (pinfunction "USART6_TX/SDIO_D6/TIM8_CH1/I2S2_MCK/PC6_96") (pintype "bidirectional"))
    )
    (net (code "124") (name "unconnected-(U17-USART6_TX{slash}SPI6_MOSI{slash}FSMC_A25{slash}PG14-Pad129)") (class "Default")
      (node (ref "U17") (pin "129") (pinfunction "USART6_TX/SPI6_MOSI/FSMC_A25/PG14_129") (pintype "bidirectional"))
    )
    (net (code "125") (name "unconnected-(U17-USBDP{slash}TIM1_ETR{slash}CAN1_TX{slash}USART1_RTS{slash}PA12-Pad104)") (class "Default")
      (node (ref "U17") (pin "104") (pinfunction "USBDP/TIM1_ETR/CAN1_TX/USART1_RTS/PA12_104") (pintype "bidirectional"))
    )
    (net (code "126") (name "unconnected-(U17-VBAT-Pad6)") (class "Default")
      (node (ref "U17") (pin "6") (pinfunction "VBAT_6") (pintype "power_in"))
    )
  )
)
